# Eurocard_VME_6U_P2.net
KiCad netlist of a schematic drawn in Altium Designer
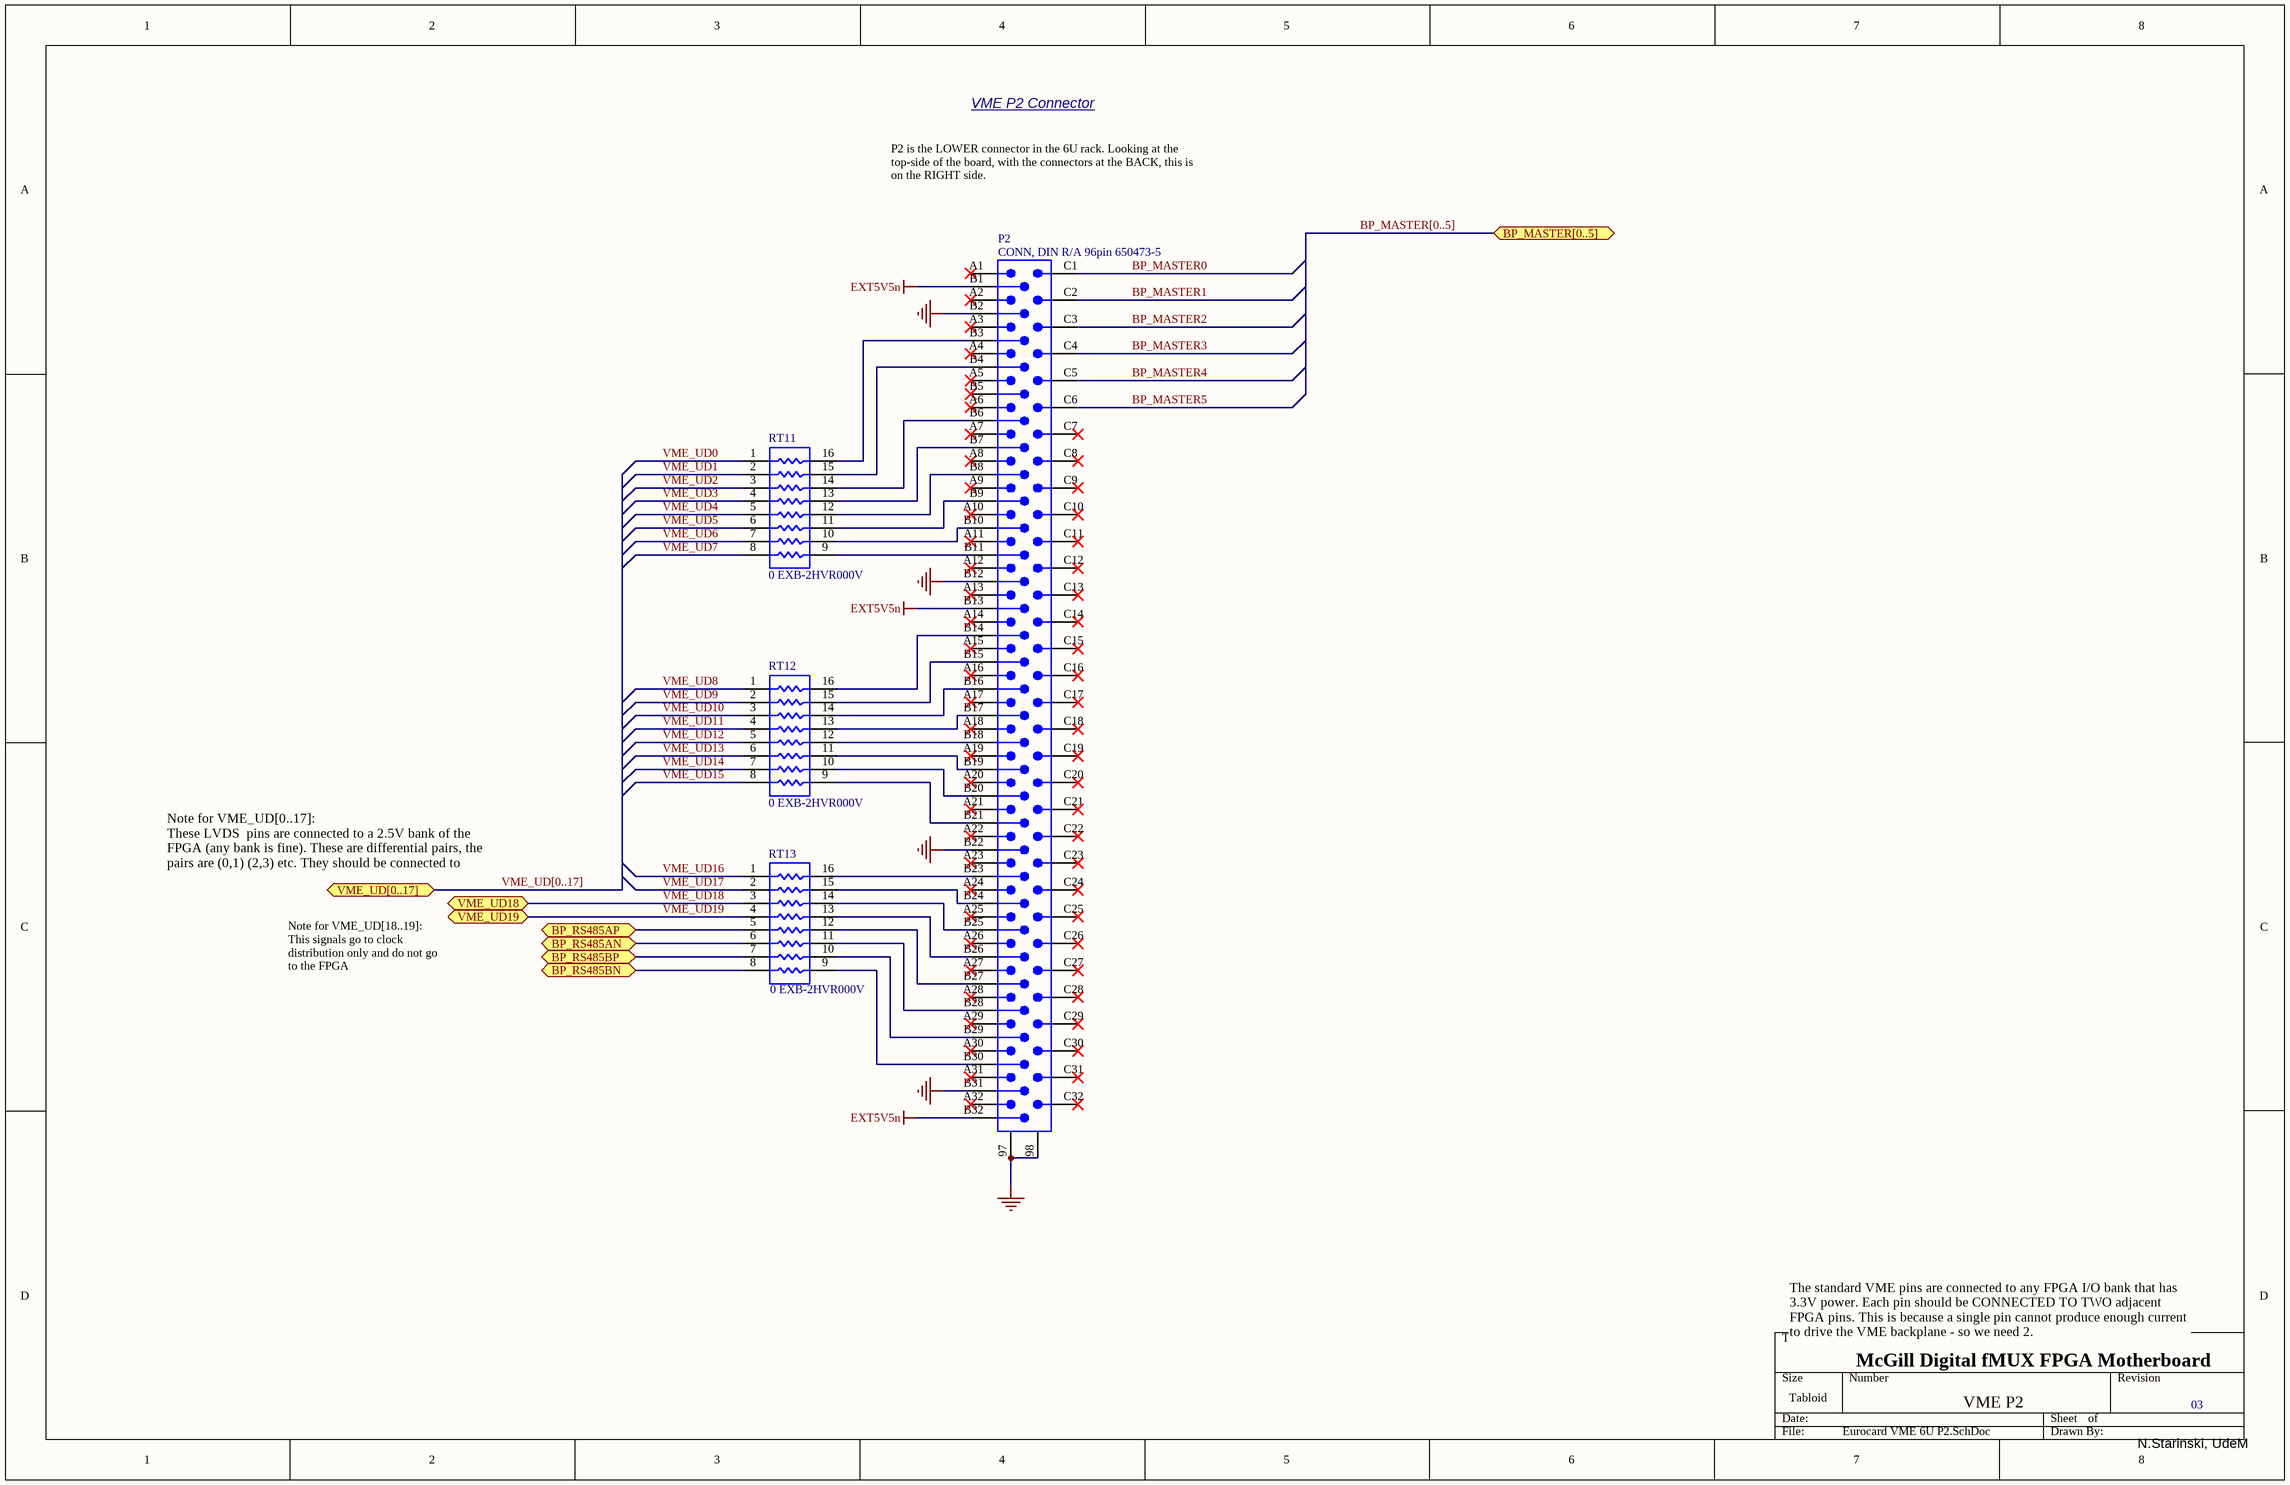
[diagram p0: Eurocard VME 6U P2.SchDoc]

(export (version "E")
  (design (tool "Eeschema 10.0.6"))
  (components
    (comp (ref "P2")
      (value "CONN, DIN R/A 96pin 650473-5")
      (footprint "CNVME96")
      (description "96-Pin Connector (3x32 2.54mm grid)")
      (libsource (lib "*") (part "CNVME96"))
    )
    (comp (ref "RT11")
      (value "0 EXB-2HVR000V")
      (description "Isolated Resistor Network")
      (fields (field (name "PUBLISHER") "Altium Limited"))
      (libsource (lib "Miscellaneous Devices 02") (part "Res Pack3"))
    )
    (comp (ref "RT12")
      (value "0 EXB-2HVR000V")
      (description "Isolated Resistor Network")
      (fields (field (name "PUBLISHER") "Altium Limited"))
      (libsource (lib "Miscellaneous Devices 02") (part "Res Pack3"))
    )
    (comp (ref "RT13")
      (value "0 EXB-2HVR000V")
      (description "Isolated Resistor Network")
      (fields (field (name "PUBLISHER") "Altium Limited"))
      (libsource (lib "Miscellaneous Devices 02") (part "Res Pack3"))
    )
  )
  (nets
    (net (code "1") (name "/BP_MASTER0") (class "Default")
      (node (ref "P2") (pin "C1") (pinfunction "C1_C1") (pintype "passive"))
    )
    (net (code "2") (name "/BP_MASTER1") (class "Default")
      (node (ref "P2") (pin "C2") (pinfunction "C2_C2") (pintype "passive"))
    )
    (net (code "3") (name "/BP_MASTER2") (class "Default")
      (node (ref "P2") (pin "C3") (pinfunction "C3_C3") (pintype "passive"))
    )
    (net (code "4") (name "/BP_MASTER3") (class "Default")
      (node (ref "P2") (pin "C4") (pinfunction "C4_C4") (pintype "passive"))
    )
    (net (code "5") (name "/BP_MASTER4") (class "Default")
      (node (ref "P2") (pin "C5") (pinfunction "C5_C5") (pintype "passive"))
    )
    (net (code "6") (name "/BP_MASTER5") (class "Default")
      (node (ref "P2") (pin "C6") (pinfunction "C6_C6") (pintype "passive"))
    )
    (net (code "8") (name "/BP_RS485AN") (class "Default")
      (node (ref "RT13") (pin "6") (pinfunction "6_6") (pintype "passive"))
    )
    (net (code "9") (name "/BP_RS485AP") (class "Default")
      (node (ref "RT13") (pin "5") (pinfunction "5_5") (pintype "passive"))
    )
    (net (code "10") (name "/BP_RS485BN") (class "Default")
      (node (ref "RT13") (pin "8") (pinfunction "8_8") (pintype "passive"))
    )
    (net (code "11") (name "/BP_RS485BP") (class "Default")
      (node (ref "RT13") (pin "7") (pinfunction "7_7") (pintype "passive"))
    )
    (net (code "12") (name "/VME_UD0") (class "Default")
      (node (ref "RT11") (pin "1") (pinfunction "1_1") (pintype "passive"))
    )
    (net (code "13") (name "/VME_UD1") (class "Default")
      (node (ref "RT11") (pin "2") (pinfunction "2_2") (pintype "passive"))
    )
    (net (code "14") (name "/VME_UD2") (class "Default")
      (node (ref "RT11") (pin "3") (pinfunction "3_3") (pintype "passive"))
    )
    (net (code "15") (name "/VME_UD3") (class "Default")
      (node (ref "RT11") (pin "4") (pinfunction "4_4") (pintype "passive"))
    )
    (net (code "16") (name "/VME_UD4") (class "Default")
      (node (ref "RT11") (pin "5") (pinfunction "5_5") (pintype "passive"))
    )
    (net (code "17") (name "/VME_UD5") (class "Default")
      (node (ref "RT11") (pin "6") (pinfunction "6_6") (pintype "passive"))
    )
    (net (code "18") (name "/VME_UD6") (class "Default")
      (node (ref "RT11") (pin "7") (pinfunction "7_7") (pintype "passive"))
    )
    (net (code "19") (name "/VME_UD7") (class "Default")
      (node (ref "RT11") (pin "8") (pinfunction "8_8") (pintype "passive"))
    )
    (net (code "20") (name "/VME_UD8") (class "Default")
      (node (ref "RT12") (pin "1") (pinfunction "1_1") (pintype "passive"))
    )
    (net (code "21") (name "/VME_UD9") (class "Default")
      (node (ref "RT12") (pin "2") (pinfunction "2_2") (pintype "passive"))
    )
    (net (code "22") (name "/VME_UD10") (class "Default")
      (node (ref "RT12") (pin "3") (pinfunction "3_3") (pintype "passive"))
    )
    (net (code "23") (name "/VME_UD11") (class "Default")
      (node (ref "RT12") (pin "4") (pinfunction "4_4") (pintype "passive"))
    )
    (net (code "24") (name "/VME_UD12") (class "Default")
      (node (ref "RT12") (pin "5") (pinfunction "5_5") (pintype "passive"))
    )
    (net (code "25") (name "/VME_UD13") (class "Default")
      (node (ref "RT12") (pin "6") (pinfunction "6_6") (pintype "passive"))
    )
    (net (code "26") (name "/VME_UD14") (class "Default")
      (node (ref "RT12") (pin "7") (pinfunction "7_7") (pintype "passive"))
    )
    (net (code "27") (name "/VME_UD15") (class "Default")
      (node (ref "RT12") (pin "8") (pinfunction "8_8") (pintype "passive"))
    )
    (net (code "28") (name "/VME_UD16") (class "Default")
      (node (ref "RT13") (pin "1") (pinfunction "1_1") (pintype "passive"))
    )
    (net (code "29") (name "/VME_UD17") (class "Default")
      (node (ref "RT13") (pin "2") (pinfunction "2_2") (pintype "passive"))
    )
    (net (code "30") (name "/VME_UD18") (class "Default")
      (node (ref "RT13") (pin "3") (pinfunction "3_3") (pintype "passive"))
    )
    (net (code "31") (name "/VME_UD19") (class "Default")
      (node (ref "RT13") (pin "4") (pinfunction "4_4") (pintype "passive"))
    )
    (net (code "33") (name "EXT5V5n") (class "Default")
      (node (ref "P2") (pin "B1") (pinfunction "B1_B1") (pintype "passive"))
      (node (ref "P2") (pin "B13") (pinfunction "B13_B13") (pintype "passive"))
      (node (ref "P2") (pin "B32") (pinfunction "B32_B32") (pintype "passive"))
    )
    (net (code "34") (name "GND") (class "Default")
      (node (ref "P2") (pin "97") (pinfunction "97_97") (pintype "passive"))
      (node (ref "P2") (pin "98") (pinfunction "98_98") (pintype "passive"))
      (node (ref "P2") (pin "B12") (pinfunction "B12_B12") (pintype "passive"))
      (node (ref "P2") (pin "B2") (pinfunction "B2_B2") (pintype "passive"))
      (node (ref "P2") (pin "B22") (pinfunction "B22_B22") (pintype "passive"))
      (node (ref "P2") (pin "B31") (pinfunction "B31_B31") (pintype "passive"))
    )
    (net (code "35") (name "Net-(P2-PadB3)") (class "Default")
      (node (ref "P2") (pin "B3") (pinfunction "B3_B3") (pintype "passive"))
      (node (ref "RT11") (pin "16") (pinfunction "16_16") (pintype "passive"))
    )
    (net (code "36") (name "Net-(P2-PadB4)") (class "Default")
      (node (ref "P2") (pin "B4") (pinfunction "B4_B4") (pintype "passive"))
      (node (ref "RT11") (pin "15") (pinfunction "15_15") (pintype "passive"))
    )
    (net (code "37") (name "Net-(P2-PadB6)") (class "Default")
      (node (ref "P2") (pin "B6") (pinfunction "B6_B6") (pintype "passive"))
      (node (ref "RT11") (pin "14") (pinfunction "14_14") (pintype "passive"))
    )
    (net (code "38") (name "Net-(P2-PadB7)") (class "Default")
      (node (ref "P2") (pin "B7") (pinfunction "B7_B7") (pintype "passive"))
      (node (ref "RT11") (pin "13") (pinfunction "13_13") (pintype "passive"))
    )
    (net (code "39") (name "Net-(P2-PadB8)") (class "Default")
      (node (ref "P2") (pin "B8") (pinfunction "B8_B8") (pintype "passive"))
      (node (ref "RT11") (pin "12") (pinfunction "12_12") (pintype "passive"))
    )
    (net (code "40") (name "Net-(P2-PadB9)") (class "Default")
      (node (ref "P2") (pin "B9") (pinfunction "B9_B9") (pintype "passive"))
      (node (ref "RT11") (pin "11") (pinfunction "11_11") (pintype "passive"))
    )
    (net (code "41") (name "Net-(P2-PadB10)") (class "Default")
      (node (ref "P2") (pin "B10") (pinfunction "B10_B10") (pintype "passive"))
      (node (ref "RT11") (pin "10") (pinfunction "10_10") (pintype "passive"))
    )
    (net (code "42") (name "Net-(P2-PadB11)") (class "Default")
      (node (ref "P2") (pin "B11") (pinfunction "B11_B11") (pintype "passive"))
      (node (ref "RT11") (pin "9") (pinfunction "9_9") (pintype "passive"))
    )
    (net (code "43") (name "Net-(P2-PadB14)") (class "Default")
      (node (ref "P2") (pin "B14") (pinfunction "B14_B14") (pintype "passive"))
      (node (ref "RT12") (pin "16") (pinfunction "16_16") (pintype "passive"))
    )
    (net (code "44") (name "Net-(P2-PadB15)") (class "Default")
      (node (ref "P2") (pin "B15") (pinfunction "B15_B15") (pintype "passive"))
      (node (ref "RT12") (pin "15") (pinfunction "15_15") (pintype "passive"))
    )
    (net (code "45") (name "Net-(P2-PadB16)") (class "Default")
      (node (ref "P2") (pin "B16") (pinfunction "B16_B16") (pintype "passive"))
      (node (ref "RT12") (pin "14") (pinfunction "14_14") (pintype "passive"))
    )
    (net (code "46") (name "Net-(P2-PadB17)") (class "Default")
      (node (ref "P2") (pin "B17") (pinfunction "B17_B17") (pintype "passive"))
      (node (ref "RT12") (pin "13") (pinfunction "13_13") (pintype "passive"))
    )
    (net (code "47") (name "Net-(P2-PadB18)") (class "Default")
      (node (ref "P2") (pin "B18") (pinfunction "B18_B18") (pintype "passive"))
      (node (ref "RT12") (pin "12") (pinfunction "12_12") (pintype "passive"))
    )
    (net (code "48") (name "Net-(P2-PadB19)") (class "Default")
      (node (ref "P2") (pin "B19") (pinfunction "B19_B19") (pintype "passive"))
      (node (ref "RT12") (pin "11") (pinfunction "11_11") (pintype "passive"))
    )
    (net (code "49") (name "Net-(P2-PadB20)") (class "Default")
      (node (ref "P2") (pin "B20") (pinfunction "B20_B20") (pintype "passive"))
      (node (ref "RT12") (pin "10") (pinfunction "10_10") (pintype "passive"))
    )
    (net (code "50") (name "Net-(P2-PadB21)") (class "Default")
      (node (ref "P2") (pin "B21") (pinfunction "B21_B21") (pintype "passive"))
      (node (ref "RT12") (pin "9") (pinfunction "9_9") (pintype "passive"))
    )
    (net (code "51") (name "Net-(P2-PadB23)") (class "Default")
      (node (ref "P2") (pin "B23") (pinfunction "B23_B23") (pintype "passive"))
      (node (ref "RT13") (pin "16") (pinfunction "16_16") (pintype "passive"))
    )
    (net (code "52") (name "Net-(P2-PadB24)") (class "Default")
      (node (ref "P2") (pin "B24") (pinfunction "B24_B24") (pintype "passive"))
      (node (ref "RT13") (pin "15") (pinfunction "15_15") (pintype "passive"))
    )
    (net (code "53") (name "Net-(P2-PadB25)") (class "Default")
      (node (ref "P2") (pin "B25") (pinfunction "B25_B25") (pintype "passive"))
      (node (ref "RT13") (pin "14") (pinfunction "14_14") (pintype "passive"))
    )
    (net (code "54") (name "Net-(P2-PadB26)") (class "Default")
      (node (ref "P2") (pin "B26") (pinfunction "B26_B26") (pintype "passive"))
      (node (ref "RT13") (pin "13") (pinfunction "13_13") (pintype "passive"))
    )
    (net (code "55") (name "Net-(P2-PadB27)") (class "Default")
      (node (ref "P2") (pin "B27") (pinfunction "B27_B27") (pintype "passive"))
      (node (ref "RT13") (pin "12") (pinfunction "12_12") (pintype "passive"))
    )
    (net (code "56") (name "Net-(P2-PadB28)") (class "Default")
      (node (ref "P2") (pin "B28") (pinfunction "B28_B28") (pintype "passive"))
      (node (ref "RT13") (pin "11") (pinfunction "11_11") (pintype "passive"))
    )
    (net (code "57") (name "Net-(P2-PadB29)") (class "Default")
      (node (ref "P2") (pin "B29") (pinfunction "B29_B29") (pintype "passive"))
      (node (ref "RT13") (pin "10") (pinfunction "10_10") (pintype "passive"))
    )
    (net (code "58") (name "Net-(P2-PadB30)") (class "Default")
      (node (ref "P2") (pin "B30") (pinfunction "B30_B30") (pintype "passive"))
      (node (ref "RT13") (pin "9") (pinfunction "9_9") (pintype "passive"))
    )
    (net (code "59") (name "unconnected-(P2-PadA1)") (class "Default")
      (node (ref "P2") (pin "A1") (pinfunction "A1_A1") (pintype "passive+no_connect"))
    )
    (net (code "60") (name "unconnected-(P2-PadA2)") (class "Default")
      (node (ref "P2") (pin "A2") (pinfunction "A2_A2") (pintype "passive+no_connect"))
    )
    (net (code "61") (name "unconnected-(P2-PadA3)") (class "Default")
      (node (ref "P2") (pin "A3") (pinfunction "A3_A3") (pintype "passive+no_connect"))
    )
    (net (code "62") (name "unconnected-(P2-PadA4)") (class "Default")
      (node (ref "P2") (pin "A4") (pinfunction "A4_A4") (pintype "passive+no_connect"))
    )
    (net (code "63") (name "unconnected-(P2-PadA5)") (class "Default")
      (node (ref "P2") (pin "A5") (pinfunction "A5_A5") (pintype "passive+no_connect"))
    )
    (net (code "64") (name "unconnected-(P2-PadA6)") (class "Default")
      (node (ref "P2") (pin "A6") (pinfunction "A6_A6") (pintype "passive+no_connect"))
    )
    (net (code "65") (name "unconnected-(P2-PadA7)") (class "Default")
      (node (ref "P2") (pin "A7") (pinfunction "A7_A7") (pintype "passive+no_connect"))
    )
    (net (code "66") (name "unconnected-(P2-PadA8)") (class "Default")
      (node (ref "P2") (pin "A8") (pinfunction "A8_A8") (pintype "passive+no_connect"))
    )
    (net (code "67") (name "unconnected-(P2-PadA9)") (class "Default")
      (node (ref "P2") (pin "A9") (pinfunction "A9_A9") (pintype "passive+no_connect"))
    )
    (net (code "68") (name "unconnected-(P2-PadA10)") (class "Default")
      (node (ref "P2") (pin "A10") (pinfunction "A10_A10") (pintype "passive+no_connect"))
    )
    (net (code "69") (name "unconnected-(P2-PadA11)") (class "Default")
      (node (ref "P2") (pin "A11") (pinfunction "A11_A11") (pintype "passive+no_connect"))
    )
    (net (code "70") (name "unconnected-(P2-PadA12)") (class "Default")
      (node (ref "P2") (pin "A12") (pinfunction "A12_A12") (pintype "passive+no_connect"))
    )
    (net (code "71") (name "unconnected-(P2-PadA13)") (class "Default")
      (node (ref "P2") (pin "A13") (pinfunction "A13_A13") (pintype "passive+no_connect"))
    )
    (net (code "72") (name "unconnected-(P2-PadA14)") (class "Default")
      (node (ref "P2") (pin "A14") (pinfunction "A14_A14") (pintype "passive+no_connect"))
    )
    (net (code "73") (name "unconnected-(P2-PadA15)") (class "Default")
      (node (ref "P2") (pin "A15") (pinfunction "A15_A15") (pintype "passive+no_connect"))
    )
    (net (code "74") (name "unconnected-(P2-PadA16)") (class "Default")
      (node (ref "P2") (pin "A16") (pinfunction "A16_A16") (pintype "passive+no_connect"))
    )
    (net (code "75") (name "unconnected-(P2-PadA17)") (class "Default")
      (node (ref "P2") (pin "A17") (pinfunction "A17_A17") (pintype "passive+no_connect"))
    )
    (net (code "76") (name "unconnected-(P2-PadA18)") (class "Default")
      (node (ref "P2") (pin "A18") (pinfunction "A18_A18") (pintype "passive+no_connect"))
    )
    (net (code "77") (name "unconnected-(P2-PadA19)") (class "Default")
      (node (ref "P2") (pin "A19") (pinfunction "A19_A19") (pintype "passive+no_connect"))
    )
    (net (code "78") (name "unconnected-(P2-PadA20)") (class "Default")
      (node (ref "P2") (pin "A20") (pinfunction "A20_A20") (pintype "passive+no_connect"))
    )
    (net (code "79") (name "unconnected-(P2-PadA21)") (class "Default")
      (node (ref "P2") (pin "A21") (pinfunction "A21_A21") (pintype "passive+no_connect"))
    )
    (net (code "80") (name "unconnected-(P2-PadA22)") (class "Default")
      (node (ref "P2") (pin "A22") (pinfunction "A22_A22") (pintype "passive+no_connect"))
    )
    (net (code "81") (name "unconnected-(P2-PadA23)") (class "Default")
      (node (ref "P2") (pin "A23") (pinfunction "A23_A23") (pintype "passive+no_connect"))
    )
    (net (code "82") (name "unconnected-(P2-PadA24)") (class "Default")
      (node (ref "P2") (pin "A24") (pinfunction "A24_A24") (pintype "passive+no_connect"))
    )
    (net (code "83") (name "unconnected-(P2-PadA25)") (class "Default")
      (node (ref "P2") (pin "A25") (pinfunction "A25_A25") (pintype "passive+no_connect"))
    )
    (net (code "84") (name "unconnected-(P2-PadA26)") (class "Default")
      (node (ref "P2") (pin "A26") (pinfunction "A26_A26") (pintype "passive+no_connect"))
    )
    (net (code "85") (name "unconnected-(P2-PadA27)") (class "Default")
      (node (ref "P2") (pin "A27") (pinfunction "A27_A27") (pintype "passive+no_connect"))
    )
    (net (code "86") (name "unconnected-(P2-PadA28)") (class "Default")
      (node (ref "P2") (pin "A28") (pinfunction "A28_A28") (pintype "passive+no_connect"))
    )
    (net (code "87") (name "unconnected-(P2-PadA29)") (class "Default")
      (node (ref "P2") (pin "A29") (pinfunction "A29_A29") (pintype "passive+no_connect"))
    )
    (net (code "88") (name "unconnected-(P2-PadA30)") (class "Default")
      (node (ref "P2") (pin "A30") (pinfunction "A30_A30") (pintype "passive+no_connect"))
    )
    (net (code "89") (name "unconnected-(P2-PadA31)") (class "Default")
      (node (ref "P2") (pin "A31") (pinfunction "A31_A31") (pintype "passive+no_connect"))
    )
    (net (code "90") (name "unconnected-(P2-PadA32)") (class "Default")
      (node (ref "P2") (pin "A32") (pinfunction "A32_A32") (pintype "passive+no_connect"))
    )
    (net (code "91") (name "unconnected-(P2-PadB5)") (class "Default")
      (node (ref "P2") (pin "B5") (pinfunction "B5_B5") (pintype "passive+no_connect"))
    )
    (net (code "92") (name "unconnected-(P2-PadC7)") (class "Default")
      (node (ref "P2") (pin "C7") (pinfunction "C7_C7") (pintype "passive+no_connect"))
    )
    (net (code "93") (name "unconnected-(P2-PadC8)") (class "Default")
      (node (ref "P2") (pin "C8") (pinfunction "C8_C8") (pintype "passive+no_connect"))
    )
    (net (code "94") (name "unconnected-(P2-PadC9)") (class "Default")
      (node (ref "P2") (pin "C9") (pinfunction "C9_C9") (pintype "passive+no_connect"))
    )
    (net (code "95") (name "unconnected-(P2-PadC10)") (class "Default")
      (node (ref "P2") (pin "C10") (pinfunction "C10_C10") (pintype "passive+no_connect"))
    )
    (net (code "96") (name "unconnected-(P2-PadC11)") (class "Default")
      (node (ref "P2") (pin "C11") (pinfunction "C11_C11") (pintype "passive+no_connect"))
    )
    (net (code "97") (name "unconnected-(P2-PadC12)") (class "Default")
      (node (ref "P2") (pin "C12") (pinfunction "C12_C12") (pintype "passive+no_connect"))
    )
    (net (code "98") (name "unconnected-(P2-PadC13)") (class "Default")
      (node (ref "P2") (pin "C13") (pinfunction "C13_C13") (pintype "passive+no_connect"))
    )
    (net (code "99") (name "unconnected-(P2-PadC14)") (class "Default")
      (node (ref "P2") (pin "C14") (pinfunction "C14_C14") (pintype "passive+no_connect"))
    )
    (net (code "100") (name "unconnected-(P2-PadC15)") (class "Default")
      (node (ref "P2") (pin "C15") (pinfunction "C15_C15") (pintype "passive+no_connect"))
    )
    (net (code "101") (name "unconnected-(P2-PadC16)") (class "Default")
      (node (ref "P2") (pin "C16") (pinfunction "C16_C16") (pintype "passive+no_connect"))
    )
    (net (code "102") (name "unconnected-(P2-PadC17)") (class "Default")
      (node (ref "P2") (pin "C17") (pinfunction "C17_C17") (pintype "passive+no_connect"))
    )
    (net (code "103") (name "unconnected-(P2-PadC18)") (class "Default")
      (node (ref "P2") (pin "C18") (pinfunction "C18_C18") (pintype "passive+no_connect"))
    )
    (net (code "104") (name "unconnected-(P2-PadC19)") (class "Default")
      (node (ref "P2") (pin "C19") (pinfunction "C19_C19") (pintype "passive+no_connect"))
    )
    (net (code "105") (name "unconnected-(P2-PadC20)") (class "Default")
      (node (ref "P2") (pin "C20") (pinfunction "C20_C20") (pintype "passive+no_connect"))
    )
    (net (code "106") (name "unconnected-(P2-PadC21)") (class "Default")
      (node (ref "P2") (pin "C21") (pinfunction "C21_C21") (pintype "passive+no_connect"))
    )
    (net (code "107") (name "unconnected-(P2-PadC22)") (class "Default")
      (node (ref "P2") (pin "C22") (pinfunction "C22_C22") (pintype "passive+no_connect"))
    )
    (net (code "108") (name "unconnected-(P2-PadC23)") (class "Default")
      (node (ref "P2") (pin "C23") (pinfunction "C23_C23") (pintype "passive+no_connect"))
    )
    (net (code "109") (name "unconnected-(P2-PadC24)") (class "Default")
      (node (ref "P2") (pin "C24") (pinfunction "C24_C24") (pintype "passive+no_connect"))
    )
    (net (code "110") (name "unconnected-(P2-PadC25)") (class "Default")
      (node (ref "P2") (pin "C25") (pinfunction "C25_C25") (pintype "passive+no_connect"))
    )
    (net (code "111") (name "unconnected-(P2-PadC26)") (class "Default")
      (node (ref "P2") (pin "C26") (pinfunction "C26_C26") (pintype "passive+no_connect"))
    )
    (net (code "112") (name "unconnected-(P2-PadC27)") (class "Default")
      (node (ref "P2") (pin "C27") (pinfunction "C27_C27") (pintype "passive+no_connect"))
    )
    (net (code "113") (name "unconnected-(P2-PadC28)") (class "Default")
      (node (ref "P2") (pin "C28") (pinfunction "C28_C28") (pintype "passive+no_connect"))
    )
    (net (code "114") (name "unconnected-(P2-PadC29)") (class "Default")
      (node (ref "P2") (pin "C29") (pinfunction "C29_C29") (pintype "passive+no_connect"))
    )
    (net (code "115") (name "unconnected-(P2-PadC30)") (class "Default")
      (node (ref "P2") (pin "C30") (pinfunction "C30_C30") (pintype "passive+no_connect"))
    )
    (net (code "116") (name "unconnected-(P2-PadC31)") (class "Default")
      (node (ref "P2") (pin "C31") (pinfunction "C31_C31") (pintype "passive+no_connect"))
    )
    (net (code "117") (name "unconnected-(P2-PadC32)") (class "Default")
      (node (ref "P2") (pin "C32") (pinfunction "C32_C32") (pintype "passive+no_connect"))
    )
  )
)
